# Gamepad.net
KiCad netlist of a schematic drawn in EAGLE
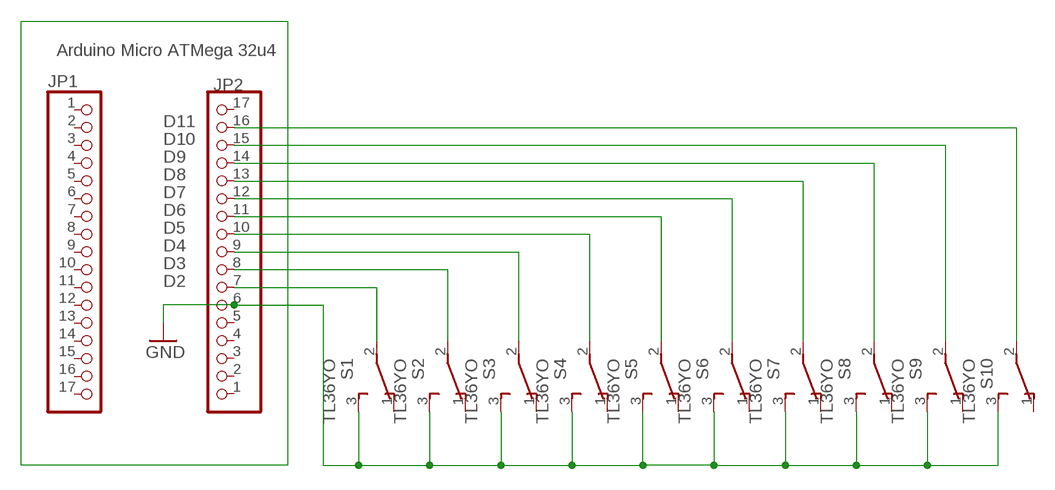
[diagram p0: schematic, sheet 1]

(export (version "E")
  (design (tool "Eeschema 10.0.6"))
  (components
    (comp (ref "JP1")
      (value "PINHD-1X17")
      (footprint "eagle-import:1X17")
      (libsource (lib "eagle-import") (part "PINHD-1X17"))
    )
    (comp (ref "JP2")
      (value "PINHD-1X17")
      (footprint "eagle-import:1X17")
      (libsource (lib "eagle-import") (part "PINHD-1X17"))
    )
    (comp (ref "S1")
      (value "TL36YO")
      (footprint "eagle-import:TL3XYO")
      (libsource (lib "eagle-import") (part "TL36YO"))
    )
    (comp (ref "S2")
      (value "TL36YO")
      (footprint "eagle-import:TL3XYO")
      (libsource (lib "eagle-import") (part "TL36YO"))
    )
    (comp (ref "S3")
      (value "TL36YO")
      (footprint "eagle-import:TL3XYO")
      (libsource (lib "eagle-import") (part "TL36YO"))
    )
    (comp (ref "S4")
      (value "TL36YO")
      (footprint "eagle-import:TL3XYO")
      (libsource (lib "eagle-import") (part "TL36YO"))
    )
    (comp (ref "S5")
      (value "TL36YO")
      (footprint "eagle-import:TL3XYO")
      (libsource (lib "eagle-import") (part "TL36YO"))
    )
    (comp (ref "S6")
      (value "TL36YO")
      (footprint "eagle-import:TL3XYO")
      (libsource (lib "eagle-import") (part "TL36YO"))
    )
    (comp (ref "S7")
      (value "TL36YO")
      (footprint "eagle-import:TL3XYO")
      (libsource (lib "eagle-import") (part "TL36YO"))
    )
    (comp (ref "S8")
      (value "TL36YO")
      (footprint "eagle-import:TL3XYO")
      (libsource (lib "eagle-import") (part "TL36YO"))
    )
    (comp (ref "S9")
      (value "TL36YO")
      (footprint "eagle-import:TL3XYO")
      (libsource (lib "eagle-import") (part "TL36YO"))
    )
    (comp (ref "S10")
      (value "TL36YO")
      (footprint "eagle-import:TL3XYO")
      (libsource (lib "eagle-import") (part "TL36YO"))
    )
  )
  (nets
    (net (code "1") (name "/D2") (class "Default")
      (node (ref "JP2") (pin "7") (pinfunction "7_7") (pintype "passive"))
      (node (ref "S1") (pin "2") (pinfunction "P_2") (pintype "passive"))
    )
    (net (code "2") (name "/D3") (class "Default")
      (node (ref "JP2") (pin "8") (pinfunction "8_8") (pintype "passive"))
      (node (ref "S2") (pin "2") (pinfunction "P_2") (pintype "passive"))
    )
    (net (code "3") (name "/D4") (class "Default")
      (node (ref "JP2") (pin "9") (pinfunction "9_9") (pintype "passive"))
      (node (ref "S3") (pin "2") (pinfunction "P_2") (pintype "passive"))
    )
    (net (code "4") (name "/D5") (class "Default")
      (node (ref "JP2") (pin "10") (pinfunction "10_10") (pintype "passive"))
      (node (ref "S4") (pin "2") (pinfunction "P_2") (pintype "passive"))
    )
    (net (code "5") (name "/D6") (class "Default")
      (node (ref "JP2") (pin "11") (pinfunction "11_11") (pintype "passive"))
      (node (ref "S5") (pin "2") (pinfunction "P_2") (pintype "passive"))
    )
    (net (code "6") (name "/D7") (class "Default")
      (node (ref "JP2") (pin "12") (pinfunction "12_12") (pintype "passive"))
      (node (ref "S6") (pin "2") (pinfunction "P_2") (pintype "passive"))
    )
    (net (code "7") (name "/D8") (class "Default")
      (node (ref "JP2") (pin "13") (pinfunction "13_13") (pintype "passive"))
      (node (ref "S7") (pin "2") (pinfunction "P_2") (pintype "passive"))
    )
    (net (code "8") (name "/D9") (class "Default")
      (node (ref "JP2") (pin "14") (pinfunction "14_14") (pintype "passive"))
      (node (ref "S8") (pin "2") (pinfunction "P_2") (pintype "passive"))
    )
    (net (code "9") (name "/D10") (class "Default")
      (node (ref "JP2") (pin "15") (pinfunction "15_15") (pintype "passive"))
      (node (ref "S9") (pin "2") (pinfunction "P_2") (pintype "passive"))
    )
    (net (code "10") (name "/D11") (class "Default")
      (node (ref "JP2") (pin "16") (pinfunction "16_16") (pintype "passive"))
      (node (ref "S10") (pin "2") (pinfunction "P_2") (pintype "passive"))
    )
    (net (code "11") (name "GND") (class "Default")
      (node (ref "JP2") (pin "6") (pinfunction "6_6") (pintype "passive"))
      (node (ref "S1") (pin "3") (pinfunction "S_3") (pintype "passive"))
      (node (ref "S10") (pin "3") (pinfunction "S_3") (pintype "passive"))
      (node (ref "S2") (pin "3") (pinfunction "S_3") (pintype "passive"))
      (node (ref "S3") (pin "3") (pinfunction "S_3") (pintype "passive"))
      (node (ref "S4") (pin "3") (pinfunction "S_3") (pintype "passive"))
      (node (ref "S5") (pin "3") (pinfunction "S_3") (pintype "passive"))
      (node (ref "S6") (pin "3") (pinfunction "S_3") (pintype "passive"))
      (node (ref "S7") (pin "3") (pinfunction "S_3") (pintype "passive"))
      (node (ref "S8") (pin "3") (pinfunction "S_3") (pintype "passive"))
      (node (ref "S9") (pin "3") (pinfunction "S_3") (pintype "passive"))
    )
    (net (code "12") (name "unconnected-(JP1-Pad1)") (class "Default")
      (node (ref "JP1") (pin "1") (pinfunction "1_1") (pintype "passive"))
    )
    (net (code "13") (name "unconnected-(JP1-Pad2)") (class "Default")
      (node (ref "JP1") (pin "2") (pinfunction "2_2") (pintype "passive"))
    )
    (net (code "14") (name "unconnected-(JP1-Pad3)") (class "Default")
      (node (ref "JP1") (pin "3") (pinfunction "3_3") (pintype "passive"))
    )
    (net (code "15") (name "unconnected-(JP1-Pad4)") (class "Default")
      (node (ref "JP1") (pin "4") (pinfunction "4_4") (pintype "passive"))
    )
    (net (code "16") (name "unconnected-(JP1-Pad5)") (class "Default")
      (node (ref "JP1") (pin "5") (pinfunction "5_5") (pintype "passive"))
    )
    (net (code "17") (name "unconnected-(JP1-Pad6)") (class "Default")
      (node (ref "JP1") (pin "6") (pinfunction "6_6") (pintype "passive"))
    )
    (net (code "18") (name "unconnected-(JP1-Pad7)") (class "Default")
      (node (ref "JP1") (pin "7") (pinfunction "7_7") (pintype "passive"))
    )
    (net (code "19") (name "unconnected-(JP1-Pad8)") (class "Default")
      (node (ref "JP1") (pin "8") (pinfunction "8_8") (pintype "passive"))
    )
    (net (code "20") (name "unconnected-(JP1-Pad9)") (class "Default")
      (node (ref "JP1") (pin "9") (pinfunction "9_9") (pintype "passive"))
    )
    (net (code "21") (name "unconnected-(JP1-Pad10)") (class "Default")
      (node (ref "JP1") (pin "10") (pinfunction "10_10") (pintype "passive"))
    )
    (net (code "22") (name "unconnected-(JP1-Pad11)") (class "Default")
      (node (ref "JP1") (pin "11") (pinfunction "11_11") (pintype "passive"))
    )
    (net (code "23") (name "unconnected-(JP1-Pad12)") (class "Default")
      (node (ref "JP1") (pin "12") (pinfunction "12_12") (pintype "passive"))
    )
    (net (code "24") (name "unconnected-(JP1-Pad13)") (class "Default")
      (node (ref "JP1") (pin "13") (pinfunction "13_13") (pintype "passive"))
    )
    (net (code "25") (name "unconnected-(JP1-Pad14)") (class "Default")
      (node (ref "JP1") (pin "14") (pinfunction "14_14") (pintype "passive"))
    )
    (net (code "26") (name "unconnected-(JP1-Pad15)") (class "Default")
      (node (ref "JP1") (pin "15") (pinfunction "15_15") (pintype "passive"))
    )
    (net (code "27") (name "unconnected-(JP1-Pad16)") (class "Default")
      (node (ref "JP1") (pin "16") (pinfunction "16_16") (pintype "passive"))
    )
    (net (code "28") (name "unconnected-(JP1-Pad17)") (class "Default")
      (node (ref "JP1") (pin "17") (pinfunction "17_17") (pintype "passive"))
    )
    (net (code "29") (name "unconnected-(JP2-Pad1)") (class "Default")
      (node (ref "JP2") (pin "1") (pinfunction "1_1") (pintype "passive"))
    )
    (net (code "30") (name "unconnected-(JP2-Pad2)") (class "Default")
      (node (ref "JP2") (pin "2") (pinfunction "2_2") (pintype "passive"))
    )
    (net (code "31") (name "unconnected-(JP2-Pad3)") (class "Default")
      (node (ref "JP2") (pin "3") (pinfunction "3_3") (pintype "passive"))
    )
    (net (code "32") (name "unconnected-(JP2-Pad4)") (class "Default")
      (node (ref "JP2") (pin "4") (pinfunction "4_4") (pintype "passive"))
    )
    (net (code "33") (name "unconnected-(JP2-Pad5)") (class "Default")
      (node (ref "JP2") (pin "5") (pinfunction "5_5") (pintype "passive"))
    )
    (net (code "34") (name "unconnected-(JP2-Pad17)") (class "Default")
      (node (ref "JP2") (pin "17") (pinfunction "17_17") (pintype "passive"))
    )
    (net (code "35") (name "unconnected-(S1-O-Pad1)") (class "Default")
      (node (ref "S1") (pin "1") (pinfunction "O_1") (pintype "passive"))
    )
    (net (code "36") (name "unconnected-(S2-O-Pad1)") (class "Default")
      (node (ref "S2") (pin "1") (pinfunction "O_1") (pintype "passive"))
    )
    (net (code "37") (name "unconnected-(S3-O-Pad1)") (class "Default")
      (node (ref "S3") (pin "1") (pinfunction "O_1") (pintype "passive"))
    )
    (net (code "38") (name "unconnected-(S4-O-Pad1)") (class "Default")
      (node (ref "S4") (pin "1") (pinfunction "O_1") (pintype "passive"))
    )
    (net (code "39") (name "unconnected-(S5-O-Pad1)") (class "Default")
      (node (ref "S5") (pin "1") (pinfunction "O_1") (pintype "passive"))
    )
    (net (code "40") (name "unconnected-(S6-O-Pad1)") (class "Default")
      (node (ref "S6") (pin "1") (pinfunction "O_1") (pintype "passive"))
    )
    (net (code "41") (name "unconnected-(S7-O-Pad1)") (class "Default")
      (node (ref "S7") (pin "1") (pinfunction "O_1") (pintype "passive"))
    )
    (net (code "42") (name "unconnected-(S8-O-Pad1)") (class "Default")
      (node (ref "S8") (pin "1") (pinfunction "O_1") (pintype "passive"))
    )
    (net (code "43") (name "unconnected-(S9-O-Pad1)") (class "Default")
      (node (ref "S9") (pin "1") (pinfunction "O_1") (pintype "passive"))
    )
    (net (code "44") (name "unconnected-(S10-O-Pad1)") (class "Default")
      (node (ref "S10") (pin "1") (pinfunction "O_1") (pintype "passive"))
    )
  )
)
